# CH32V467WEU-R0.net
KiCad netlist of a schematic drawn in Altium Designer
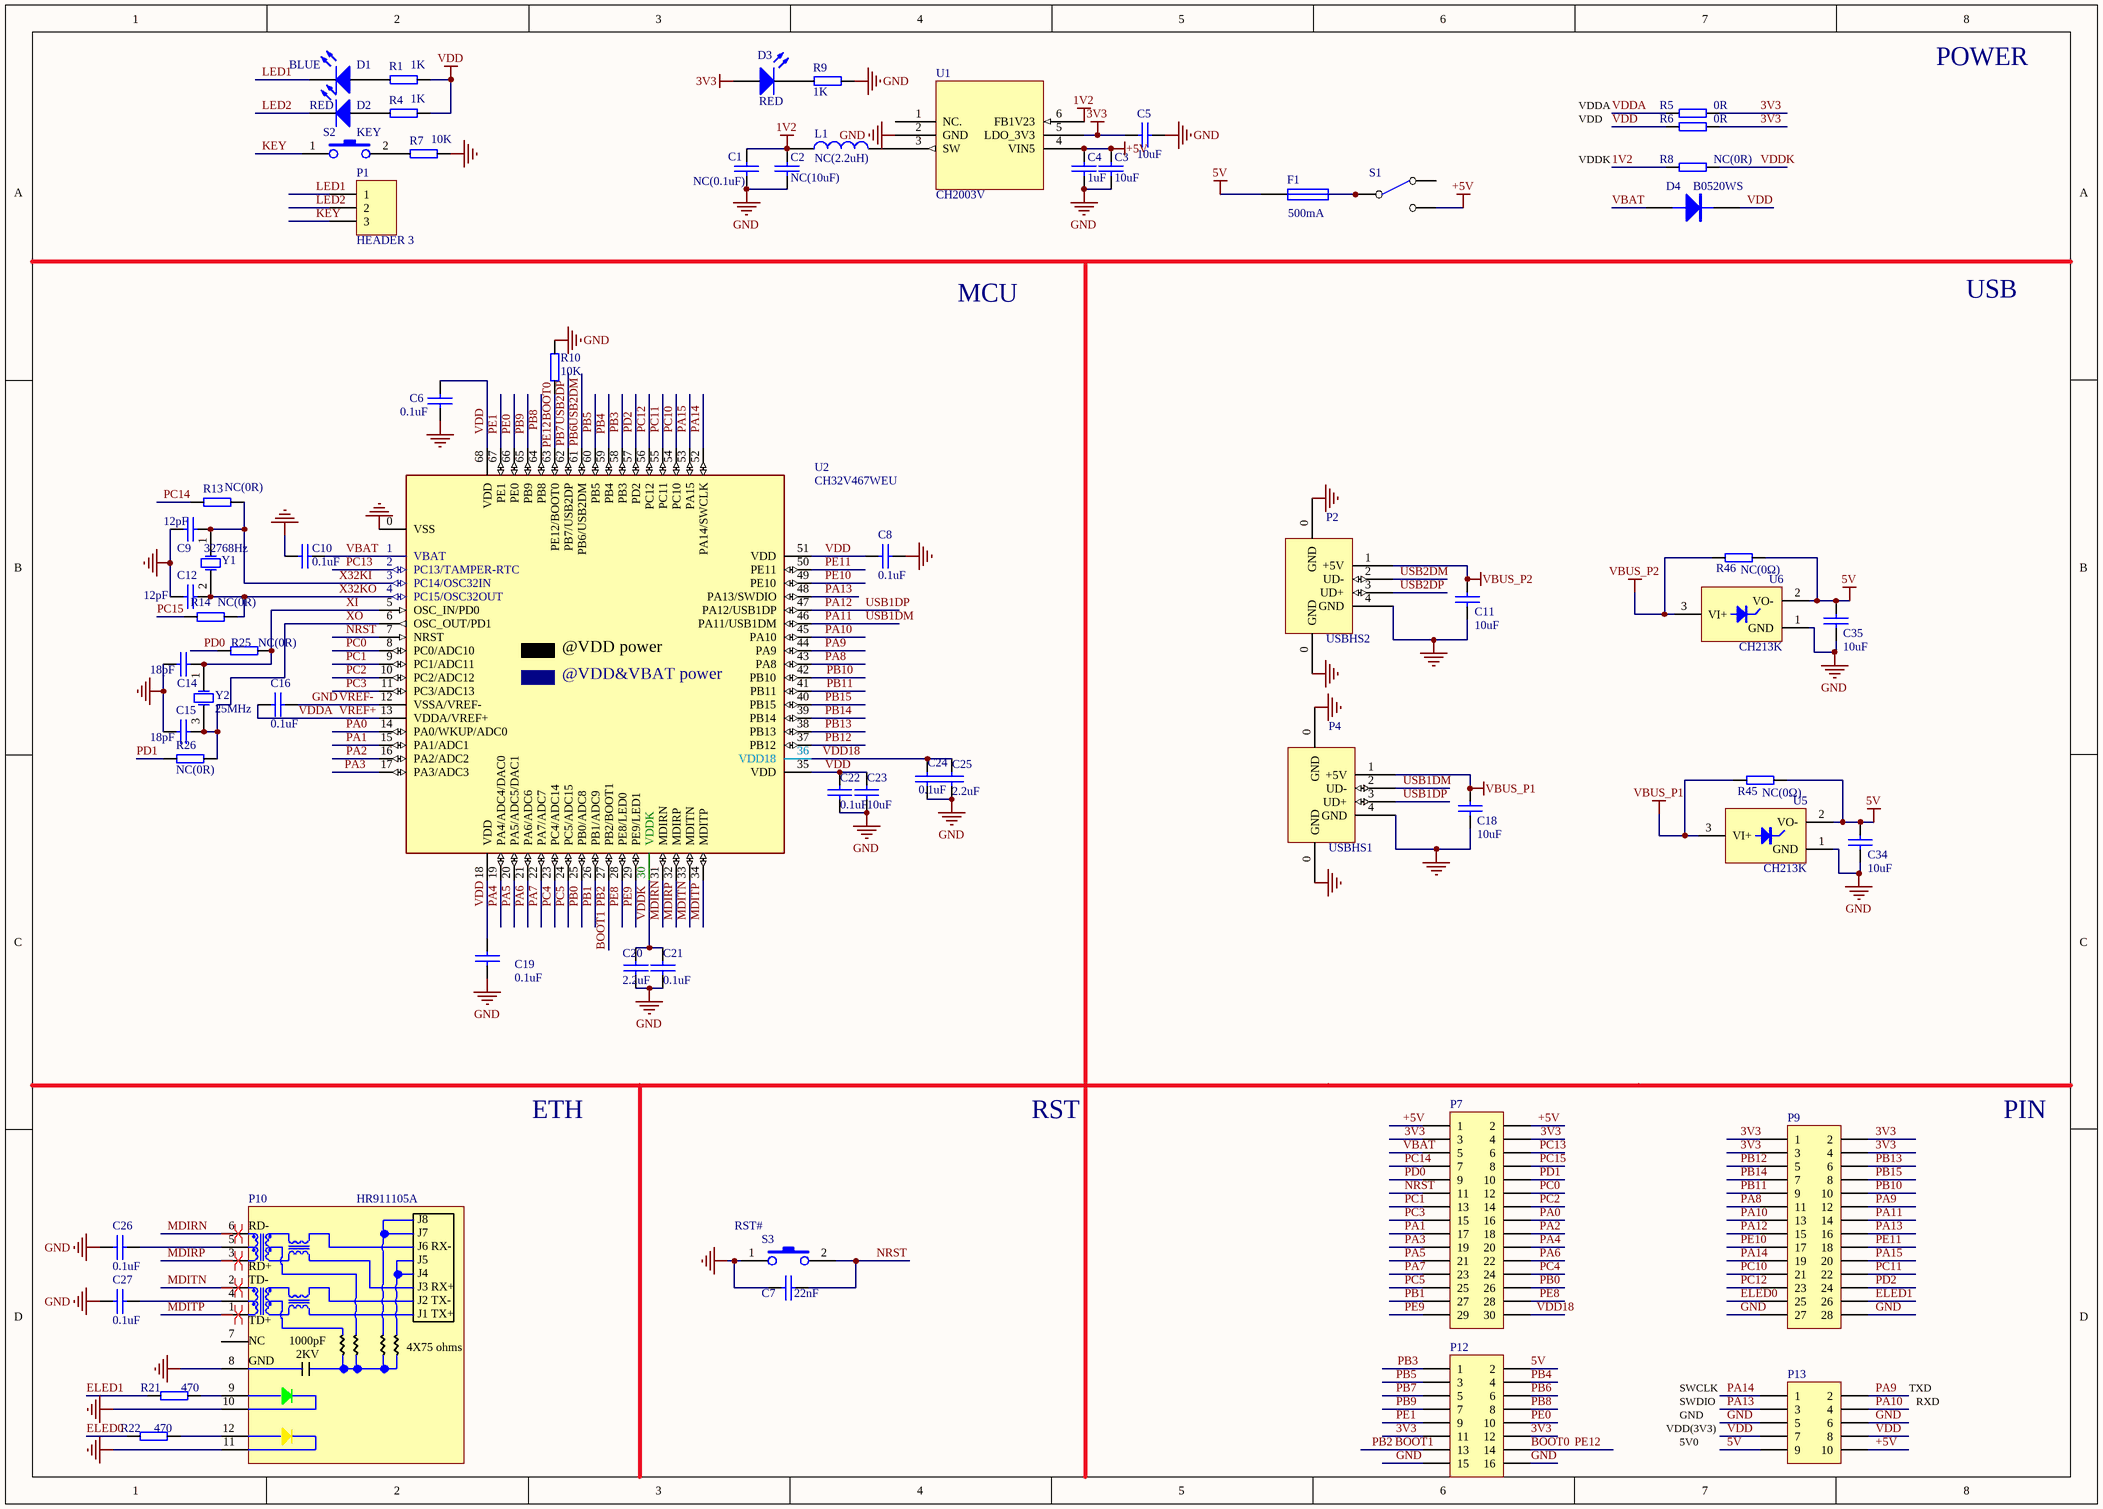
[diagram p0: CH32V467WEU-R0.SchDoc]

(export (version "E")
  (design (tool "Eeschema 10.0.6"))
  (components
    (comp (ref "C1")
      (value "NC(0.1uF)")
      (footprint "0402_C")
      (description "Capacitor")
      (libsource (lib "") (part "CAP_2"))
    )
    (comp (ref "C2")
      (value "NC(10uF)")
      (footprint "0603_C")
      (description "Capacitor")
      (libsource (lib "*") (part "CAP"))
    )
    (comp (ref "C3")
      (value "10uF")
      (footprint "0603_C")
      (description "Capacitor")
      (libsource (lib "*") (part "CAP"))
    )
    (comp (ref "C4")
      (value "1uF")
      (footprint "0402_C")
      (description "Capacitor")
      (libsource (lib "") (part "CAP_2"))
    )
    (comp (ref "C5")
      (value "10uF")
      (footprint "0603_C")
      (description "Capacitor")
      (libsource (lib "*") (part "CAP"))
    )
    (comp (ref "C6")
      (value "0.1uF")
      (footprint "0402_C")
      (description "Capacitor")
      (libsource (lib "*") (part "CAP"))
    )
    (comp (ref "C7")
      (value "22nF")
      (footprint "0402_C")
      (description "Capacitor")
      (libsource (lib "") (part "CAP_1"))
    )
    (comp (ref "C8")
      (value "0.1uF")
      (footprint "0402_C")
      (description "Capacitor")
      (libsource (lib "*") (part "CAP"))
    )
    (comp (ref "C9")
      (value "12pF")
      (footprint "0402_C")
      (description "Capacitor")
      (libsource (lib "*") (part "CAP"))
    )
    (comp (ref "C10")
      (value "0.1uF")
      (footprint "0402_C")
      (description "Capacitor")
      (libsource (lib "*") (part "CAP"))
    )
    (comp (ref "C11")
      (value "10uF")
      (footprint "0603_C")
      (description "Capacitor")
      (libsource (lib "") (part "CAP_1"))
    )
    (comp (ref "C12")
      (value "12pF")
      (footprint "0402_C")
      (description "Capacitor")
      (libsource (lib "*") (part "CAP"))
    )
    (comp (ref "C14")
      (value "18pF")
      (footprint "0402_C")
      (description "Capacitor")
      (libsource (lib "*") (part "CAP"))
    )
    (comp (ref "C15")
      (value "18pF")
      (footprint "0402_C")
      (description "Capacitor")
      (libsource (lib "*") (part "CAP"))
    )
    (comp (ref "C16")
      (value "0.1uF")
      (footprint "0402_C")
      (description "Capacitor")
      (libsource (lib "*") (part "CAP"))
    )
    (comp (ref "C18")
      (value "10uF")
      (footprint "0603_C")
      (description "Capacitor")
      (libsource (lib "") (part "CAP_1"))
    )
    (comp (ref "C19")
      (value "0.1uF")
      (footprint "0402_C")
      (description "Capacitor")
      (libsource (lib "*") (part "CAP"))
    )
    (comp (ref "C20")
      (value "2.2uF")
      (footprint "0402_C")
      (description "Capacitor")
      (libsource (lib "*") (part "CAP"))
    )
    (comp (ref "C21")
      (value "0.1uF")
      (footprint "0402_C")
      (description "Capacitor")
      (libsource (lib "*") (part "CAP"))
    )
    (comp (ref "C22")
      (value "0.1uF")
      (footprint "0402_C")
      (description "Capacitor")
      (libsource (lib "*") (part "CAP"))
    )
    (comp (ref "C23")
      (value "10uF")
      (footprint "0603_C")
      (description "Capacitor")
      (libsource (lib "*") (part "CAP"))
    )
    (comp (ref "C24")
      (value "0.1uF")
      (footprint "0402_C")
      (description "Capacitor")
      (libsource (lib "*") (part "CAP"))
    )
    (comp (ref "C25")
      (value "2.2uF")
      (footprint "0402_C")
      (description "Capacitor")
      (libsource (lib "*") (part "CAP"))
    )
    (comp (ref "C26")
      (value "0.1uF")
      (footprint "0402_C")
      (description "Capacitor")
      (libsource (lib "wch_sch_others") (part "CAP"))
    )
    (comp (ref "C27")
      (value "0.1uF")
      (footprint "0402_C")
      (description "Capacitor")
      (libsource (lib "wch_sch_others") (part "CAP"))
    )
    (comp (ref "C34")
      (value "10uF")
      (footprint "0603_C")
      (description "Capacitor")
      (libsource (lib "") (part "CAP_1"))
    )
    (comp (ref "C35")
      (value "10uF")
      (footprint "0603_C")
      (description "Capacitor")
      (libsource (lib "") (part "CAP_1"))
    )
    (comp (ref "D1")
      (value "BLUE")
      (footprint "0603+")
      (description "Typical INFRARED GaAs LED")
      (fields (field (name "PUBLISHER") "Altium Limited"))
      (libsource (lib "*") (part "LED0"))
    )
    (comp (ref "D2")
      (value "RED")
      (footprint "0603+")
      (description "Typical INFRARED GaAs LED")
      (fields (field (name "PUBLISHER") "Altium Limited"))
      (libsource (lib "*") (part "LED0"))
    )
    (comp (ref "D3")
      (value "RED")
      (footprint "0603+")
      (description "Typical INFRARED GaAs LED")
      (fields (field (name "PUBLISHER") "Altium Limited"))
      (libsource (lib "*") (part "LED0"))
    )
    (comp (ref "D4")
      (value "B0520WS")
      (footprint "SOD-323")
      (description "Diode")
      (libsource (lib "*") (part "DIODE"))
    )
    (comp (ref "F1")
      (value "500mA")
      (footprint "0603")
      (description "Fuse")
      (libsource (lib "wch_sch_others") (part "FUSE1"))
    )
    (comp (ref "L1") (value "NC(2.2uH)") (footprint "CD32") (libsource (lib "*") (part "INDUCTOR")))
    (comp (ref "P1")
      (value "HEADER 3")
      (footprint "SIP3-2.54MM")
      (description "Header, 3-Pin")
      (libsource (lib "wch_sch_others") (part "HEADER 3"))
    )
    (comp (ref "P2")
      (value "USBHS2")
      (footprint "USBAF")
      (description "USB Port")
      (libsource (lib "*") (part "USB"))
    )
    (comp (ref "P4")
      (value "USBHS1")
      (footprint "USBAF")
      (description "USB Port")
      (libsource (lib "*") (part "USB"))
    )
    (comp (ref "P7")
      (value "HEADER 15x2")
      (footprint "MYPCB:IDC30-2.54MM")
      (description "Header, 15-Pin, Dual row")
      (libsource (lib "wch_sch_others") (part "HEADER 15x2"))
    )
    (comp (ref "P9")
      (value "HEADER 14x2")
      (footprint "MYPCB:IDC28-2.54MM")
      (description "Header, 14-Pin, Dual row")
      (libsource (lib "wch_sch_others") (part "HEADER 14x2"))
    )
    (comp (ref "P10") (value "HR911105A") (footprint "HR911105A") (libsource (lib "*") (part "HR911105A")))
    (comp (ref "P12")
      (value "Ppin")
      (footprint "IDC16-2.54mm")
      (description "Header, 8-Pin, Dual row, Right Angle")
      (fields (field (name "PUBLISHER") "Altium Limited"))
      (libsource (lib "Miscellaneous Connectors") (part "Header 8X2H"))
    )
    (comp (ref "P13")
      (value "LINK")
      (footprint "IDC10-2.54mm")
      (description "Header, 5-Pin, Dual row, Right Angle")
      (fields (field (name "PUBLISHER") "Altium Limited"))
      (libsource (lib "Miscellaneous Connectors") (part "Header 5X2H"))
    )
    (comp (ref "R1") (value "1K") (footprint "0402") (libsource (lib "wch_sch_others") (part "RES")))
    (comp (ref "R4") (value "1K") (footprint "0402") (libsource (lib "wch_sch_others") (part "RES")))
    (comp (ref "R5") (value "0R") (footprint "0402") (libsource (lib "*") (part "R")))
    (comp (ref "R6") (value "0R") (footprint "0402") (libsource (lib "*") (part "R")))
    (comp (ref "R7") (value "10K") (footprint "0402") (libsource (lib "wch_sch_others") (part "RES")))
    (comp (ref "R8") (value "NC(0R)") (footprint "0402") (libsource (lib "*") (part "R")))
    (comp (ref "R9") (value "1K") (footprint "0402") (libsource (lib "wch_sch_others") (part "RES")))
    (comp (ref "R10") (value "10K") (footprint "0402") (libsource (lib "wch_sch_others") (part "RES")))
    (comp (ref "R13") (value "NC(0R)") (footprint "0402") (libsource (lib "wch_sch_others") (part "RES")))
    (comp (ref "R14") (value "NC(0R)") (footprint "0402") (libsource (lib "wch_sch_others") (part "RES")))
    (comp (ref "R21") (value "470") (footprint "0402") (libsource (lib "wch_sch_others") (part "RES")))
    (comp (ref "R22") (value "470") (footprint "0402") (libsource (lib "wch_sch_others") (part "RES")))
    (comp (ref "R25") (value "NC(0R)") (footprint "0402") (libsource (lib "wch_sch_others") (part "RES")))
    (comp (ref "R26") (value "NC(0R)") (footprint "0402") (libsource (lib "wch_sch_others") (part "RES")))
    (comp (ref "R45") (value "NC(0Ω)") (footprint "0402") (libsource (lib "wch_sch_others") (part "RES")))
    (comp (ref "R46") (value "NC(0Ω)") (footprint "0402") (libsource (lib "wch_sch_others") (part "RES")))
    (comp (ref "S1") (value "SW SPDT") (footprint "SW1") (libsource (lib "*") (part "SW SPDT")))
    (comp (ref "S2")
      (value "KEY")
      (footprint "SMD_6.1x3.65x2.5mm-KEY")
      (libsource (lib "wch_sch_others") (part "KEY1"))
    )
    (comp (ref "S3")
      (value "RST#")
      (footprint "SMD_6.1x3.65x2.5mm-KEY")
      (libsource (lib "wch_sch_others") (part "KEY1"))
    )
    (comp (ref "U1")
      (value "CH2003V")
      (footprint "SOT-23-6")
      (description "Step-Down DC-DC Converter, 5V input, 1.23V * 800mA output, with LDO 3.3V * 200mA")
      (libsource (lib "CHXXX") (part "CH2003V"))
    )
    (comp (ref "U2")
      (value "CH32V467WEU")
      (footprint "QFN68_8X8")
      (description "RISC-V FPU HD-MCU, 175MHz, USB_480M, 100M Ethernet & Phy, CAN, ADC, DAC, SRAM")
      (libsource (lib "CHXXX") (part "CH32V467WEU"))
    )
    (comp (ref "U5")
      (value "CH213K")
      (footprint "SOT-23-3")
      (description "Ideal Diode 5V*1A")
      (libsource (lib "*") (part "CH213K"))
    )
    (comp (ref "U6")
      (value "CH213K")
      (footprint "SOT-23-3")
      (description "Ideal Diode 5V*1A")
      (libsource (lib "*") (part "CH213K"))
    )
    (comp (ref "Y1")
      (value "32768Hz")
      (footprint "FC-135")
      (description "Crystal Oscillator")
      (fields (field (name "PUBLISHER") "Altium Limited"))
      (libsource (lib "") (part "XTAL_1"))
    )
    (comp (ref "Y2")
      (value "25MHz")
      (footprint "XT3225")
      (description "Crystal Oscillator")
      (fields (field (name "PUBLISHER") "Altium Limited"))
      (libsource (lib "*") (part "XTAL"))
    )
  )
  (nets
    (net (code "1") (name "+5V") (class "Default")
      (node (ref "C3") (pin "2") (pinfunction "2_2") (pintype "passive"))
      (node (ref "C4") (pin "2") (pinfunction "2_2") (pintype "passive"))
      (node (ref "P13") (pin "10") (pinfunction "10_10") (pintype "passive"))
      (node (ref "P7") (pin "1") (pinfunction "1_1") (pintype "passive"))
      (node (ref "P7") (pin "2") (pinfunction "2_2") (pintype "passive"))
      (node (ref "S1") (pin "2") (pinfunction "NC_2") (pintype "passive"))
      (node (ref "U1") (pin "4") (pinfunction "VIN5_4") (pintype "power_in"))
    )
    (net (code "3") (name "/BOOT0") (class "Default")
      (node (ref "P12") (pin "14") (pinfunction "14_14") (pintype "passive"))
      (node (ref "R10") (pin "2") (pintype "passive"))
      (node (ref "U2") (pin "63") (pinfunction "PE12/BOOT0_63") (pintype "bidirectional"))
    )
    (net (code "4") (name "/BOOT1") (class "Default")
      (node (ref "P12") (pin "13") (pinfunction "13_13") (pintype "passive"))
      (node (ref "U2") (pin "27") (pinfunction "PB2/BOOT1_27") (pintype "bidirectional"))
    )
    (net (code "5") (name "/ELED0") (class "Default")
      (node (ref "P9") (pin "25") (pinfunction "25_25") (pintype "passive"))
      (node (ref "R22") (pin "1") (pintype "passive"))
    )
    (net (code "6") (name "/ELED1") (class "Default")
      (node (ref "P9") (pin "26") (pinfunction "26_26") (pintype "passive"))
      (node (ref "R21") (pin "1") (pintype "passive"))
    )
    (net (code "7") (name "/KEY") (class "Default")
      (node (ref "P1") (pin "3") (pinfunction "3_3") (pintype "passive"))
      (node (ref "S2") (pin "1") (pinfunction "1_1") (pintype "passive"))
    )
    (net (code "8") (name "/LED1") (class "Default")
      (node (ref "D1") (pin "2") (pinfunction "K_2") (pintype "passive"))
      (node (ref "P1") (pin "1") (pinfunction "1_1") (pintype "passive"))
    )
    (net (code "9") (name "/LED2") (class "Default")
      (node (ref "D2") (pin "2") (pinfunction "K_2") (pintype "passive"))
      (node (ref "P1") (pin "2") (pinfunction "2_2") (pintype "passive"))
    )
    (net (code "10") (name "/MDIRN") (class "Default")
      (node (ref "P10") (pin "6") (pintype "passive"))
      (node (ref "U2") (pin "31") (pinfunction "MDIRN_31") (pintype "bidirectional"))
    )
    (net (code "11") (name "/MDIRP") (class "Default")
      (node (ref "P10") (pin "3") (pintype "passive"))
      (node (ref "U2") (pin "32") (pinfunction "MDIRP_32") (pintype "bidirectional"))
    )
    (net (code "12") (name "/MDITN") (class "Default")
      (node (ref "P10") (pin "2") (pintype "passive"))
      (node (ref "U2") (pin "33") (pinfunction "MDITN_33") (pintype "bidirectional"))
    )
    (net (code "13") (name "/MDITP") (class "Default")
      (node (ref "P10") (pin "1") (pintype "passive"))
      (node (ref "U2") (pin "34") (pinfunction "MDITP_34") (pintype "bidirectional"))
    )
    (net (code "14") (name "/NRST") (class "Default")
      (node (ref "C7") (pin "2") (pinfunction "2_2") (pintype "passive"))
      (node (ref "P7") (pin "11") (pinfunction "11_11") (pintype "passive"))
      (node (ref "S3") (pin "2") (pinfunction "2_2") (pintype "passive"))
      (node (ref "U2") (pin "7") (pinfunction "NRST_7") (pintype "input"))
    )
    (net (code "15") (name "/PA0") (class "Default")
      (node (ref "P7") (pin "16") (pinfunction "16_16") (pintype "passive"))
      (node (ref "U2") (pin "14") (pinfunction "PA0/WKUP/ADC0_14") (pintype "bidirectional"))
    )
    (net (code "16") (name "/PA1") (class "Default")
      (node (ref "P7") (pin "17") (pinfunction "17_17") (pintype "passive"))
      (node (ref "U2") (pin "15") (pinfunction "PA1/ADC1_15") (pintype "bidirectional"))
    )
    (net (code "17") (name "/PA2") (class "Default")
      (node (ref "P7") (pin "18") (pinfunction "18_18") (pintype "passive"))
      (node (ref "U2") (pin "16") (pinfunction "PA2/ADC2_16") (pintype "bidirectional"))
    )
    (net (code "18") (name "/PA3") (class "Default")
      (node (ref "P7") (pin "19") (pinfunction "19_19") (pintype "passive"))
      (node (ref "U2") (pin "17") (pinfunction "PA3/ADC3_17") (pintype "bidirectional"))
    )
    (net (code "19") (name "/PA4") (class "Default")
      (node (ref "P7") (pin "20") (pinfunction "20_20") (pintype "passive"))
      (node (ref "U2") (pin "19") (pinfunction "PA4/ADC4/DAC0_19") (pintype "bidirectional"))
    )
    (net (code "20") (name "/PA5") (class "Default")
      (node (ref "P7") (pin "21") (pinfunction "21_21") (pintype "passive"))
      (node (ref "U2") (pin "20") (pinfunction "PA5/ADC5/DAC1_20") (pintype "bidirectional"))
    )
    (net (code "21") (name "/PA6") (class "Default")
      (node (ref "P7") (pin "22") (pinfunction "22_22") (pintype "passive"))
      (node (ref "U2") (pin "21") (pinfunction "PA6/ADC6_21") (pintype "bidirectional"))
    )
    (net (code "22") (name "/PA7") (class "Default")
      (node (ref "P7") (pin "23") (pinfunction "23_23") (pintype "passive"))
      (node (ref "U2") (pin "22") (pinfunction "PA7/ADC7_22") (pintype "bidirectional"))
    )
    (net (code "23") (name "/PA8") (class "Default")
      (node (ref "P9") (pin "11") (pinfunction "11_11") (pintype "passive"))
      (node (ref "U2") (pin "43") (pinfunction "PA8_43") (pintype "bidirectional"))
    )
    (net (code "24") (name "/PA9") (class "Default")
      (node (ref "P13") (pin "2") (pinfunction "2_2") (pintype "passive"))
      (node (ref "P9") (pin "12") (pinfunction "12_12") (pintype "passive"))
      (node (ref "U2") (pin "44") (pinfunction "PA9_44") (pintype "bidirectional"))
    )
    (net (code "25") (name "/PA10") (class "Default")
      (node (ref "P13") (pin "4") (pinfunction "4_4") (pintype "passive"))
      (node (ref "P9") (pin "13") (pinfunction "13_13") (pintype "passive"))
      (node (ref "U2") (pin "45") (pinfunction "PA10_45") (pintype "bidirectional"))
    )
    (net (code "26") (name "/PA11") (class "Default")
      (node (ref "P4") (pin "2") (pinfunction "UD-_2") (pintype "bidirectional"))
      (node (ref "P9") (pin "14") (pinfunction "14_14") (pintype "passive"))
      (node (ref "U2") (pin "46") (pinfunction "PA11/USB1DM_46") (pintype "bidirectional"))
    )
    (net (code "27") (name "/PA12") (class "Default")
      (node (ref "P4") (pin "3") (pinfunction "UD+_3") (pintype "bidirectional"))
      (node (ref "P9") (pin "15") (pinfunction "15_15") (pintype "passive"))
      (node (ref "U2") (pin "47") (pinfunction "PA12/USB1DP_47") (pintype "bidirectional"))
    )
    (net (code "28") (name "/PA13") (class "Default")
      (node (ref "P13") (pin "3") (pinfunction "3_3") (pintype "passive"))
      (node (ref "P9") (pin "16") (pinfunction "16_16") (pintype "passive"))
      (node (ref "U2") (pin "48") (pinfunction "PA13/SWDIO_48") (pintype "bidirectional"))
    )
    (net (code "29") (name "/PA14") (class "Default")
      (node (ref "P13") (pin "1") (pinfunction "1_1") (pintype "passive"))
      (node (ref "P9") (pin "19") (pinfunction "19_19") (pintype "passive"))
      (node (ref "U2") (pin "52") (pinfunction "PA14/SWCLK_52") (pintype "bidirectional"))
    )
    (net (code "30") (name "/PA15") (class "Default")
      (node (ref "P9") (pin "20") (pinfunction "20_20") (pintype "passive"))
      (node (ref "U2") (pin "53") (pinfunction "PA15_53") (pintype "bidirectional"))
    )
    (net (code "31") (name "/PB0") (class "Default")
      (node (ref "P7") (pin "26") (pinfunction "26_26") (pintype "passive"))
      (node (ref "U2") (pin "25") (pinfunction "PB0/ADC8_25") (pintype "bidirectional"))
    )
    (net (code "32") (name "/PB1") (class "Default")
      (node (ref "P7") (pin "27") (pinfunction "27_27") (pintype "passive"))
      (node (ref "U2") (pin "26") (pinfunction "PB1/ADC9_26") (pintype "bidirectional"))
    )
    (net (code "33") (name "/PB3") (class "Default")
      (node (ref "P12") (pin "1") (pinfunction "1_1") (pintype "passive"))
      (node (ref "U2") (pin "58") (pinfunction "PB3_58") (pintype "bidirectional"))
    )
    (net (code "34") (name "/PB4") (class "Default")
      (node (ref "P12") (pin "4") (pinfunction "4_4") (pintype "passive"))
      (node (ref "U2") (pin "59") (pinfunction "PB4_59") (pintype "bidirectional"))
    )
    (net (code "35") (name "/PB5") (class "Default")
      (node (ref "P12") (pin "3") (pinfunction "3_3") (pintype "passive"))
      (node (ref "U2") (pin "60") (pinfunction "PB5_60") (pintype "bidirectional"))
    )
    (net (code "36") (name "/PB6") (class "Default")
      (node (ref "P12") (pin "6") (pinfunction "6_6") (pintype "passive"))
      (node (ref "P2") (pin "2") (pinfunction "UD-_2") (pintype "bidirectional"))
      (node (ref "U2") (pin "61") (pinfunction "PB6/USB2DM_61") (pintype "bidirectional"))
    )
    (net (code "37") (name "/PB7") (class "Default")
      (node (ref "P12") (pin "5") (pinfunction "5_5") (pintype "passive"))
      (node (ref "P2") (pin "3") (pinfunction "UD+_3") (pintype "bidirectional"))
      (node (ref "U2") (pin "62") (pinfunction "PB7/USB2DP_62") (pintype "bidirectional"))
    )
    (net (code "38") (name "/PB8") (class "Default")
      (node (ref "P12") (pin "8") (pinfunction "8_8") (pintype "passive"))
      (node (ref "U2") (pin "64") (pinfunction "PB8_64") (pintype "bidirectional"))
    )
    (net (code "39") (name "/PB9") (class "Default")
      (node (ref "P12") (pin "7") (pinfunction "7_7") (pintype "passive"))
      (node (ref "U2") (pin "65") (pinfunction "PB9_65") (pintype "bidirectional"))
    )
    (net (code "40") (name "/PB10") (class "Default")
      (node (ref "P9") (pin "10") (pinfunction "10_10") (pintype "passive"))
      (node (ref "U2") (pin "42") (pinfunction "PB10_42") (pintype "bidirectional"))
    )
    (net (code "41") (name "/PB11") (class "Default")
      (node (ref "P9") (pin "9") (pinfunction "9_9") (pintype "passive"))
      (node (ref "U2") (pin "41") (pinfunction "PB11_41") (pintype "bidirectional"))
    )
    (net (code "42") (name "/PB12") (class "Default")
      (node (ref "P9") (pin "5") (pinfunction "5_5") (pintype "passive"))
      (node (ref "U2") (pin "37") (pinfunction "PB12_37") (pintype "bidirectional"))
    )
    (net (code "43") (name "/PB13") (class "Default")
      (node (ref "P9") (pin "6") (pinfunction "6_6") (pintype "passive"))
      (node (ref "U2") (pin "38") (pinfunction "PB13_38") (pintype "bidirectional"))
    )
    (net (code "44") (name "/PB14") (class "Default")
      (node (ref "P9") (pin "7") (pinfunction "7_7") (pintype "passive"))
      (node (ref "U2") (pin "39") (pinfunction "PB14_39") (pintype "bidirectional"))
    )
    (net (code "45") (name "/PB15") (class "Default")
      (node (ref "P9") (pin "8") (pinfunction "8_8") (pintype "passive"))
      (node (ref "U2") (pin "40") (pinfunction "PB15_40") (pintype "bidirectional"))
    )
    (net (code "46") (name "/PC0") (class "Default")
      (node (ref "P7") (pin "12") (pinfunction "12_12") (pintype "passive"))
      (node (ref "U2") (pin "8") (pinfunction "PC0/ADC10_8") (pintype "bidirectional"))
    )
    (net (code "47") (name "/PC1") (class "Default")
      (node (ref "P7") (pin "13") (pinfunction "13_13") (pintype "passive"))
      (node (ref "U2") (pin "9") (pinfunction "PC1/ADC11_9") (pintype "bidirectional"))
    )
    (net (code "48") (name "/PC2") (class "Default")
      (node (ref "P7") (pin "14") (pinfunction "14_14") (pintype "passive"))
      (node (ref "U2") (pin "10") (pinfunction "PC2/ADC12_10") (pintype "bidirectional"))
    )
    (net (code "49") (name "/PC3") (class "Default")
      (node (ref "P7") (pin "15") (pinfunction "15_15") (pintype "passive"))
      (node (ref "U2") (pin "11") (pinfunction "PC3/ADC13_11") (pintype "bidirectional"))
    )
    (net (code "50") (name "/PC4") (class "Default")
      (node (ref "P7") (pin "24") (pinfunction "24_24") (pintype "passive"))
      (node (ref "U2") (pin "23") (pinfunction "PC4/ADC14_23") (pintype "bidirectional"))
    )
    (net (code "51") (name "/PC5") (class "Default")
      (node (ref "P7") (pin "25") (pinfunction "25_25") (pintype "passive"))
      (node (ref "U2") (pin "24") (pinfunction "PC5/ADC15_24") (pintype "bidirectional"))
    )
    (net (code "52") (name "/PC10") (class "Default")
      (node (ref "P9") (pin "21") (pinfunction "21_21") (pintype "passive"))
      (node (ref "U2") (pin "54") (pinfunction "PC10_54") (pintype "bidirectional"))
    )
    (net (code "53") (name "/PC11") (class "Default")
      (node (ref "P9") (pin "22") (pinfunction "22_22") (pintype "passive"))
      (node (ref "U2") (pin "55") (pinfunction "PC11_55") (pintype "bidirectional"))
    )
    (net (code "54") (name "/PC12") (class "Default")
      (node (ref "P9") (pin "23") (pinfunction "23_23") (pintype "passive"))
      (node (ref "U2") (pin "56") (pinfunction "PC12_56") (pintype "bidirectional"))
    )
    (net (code "55") (name "/PC13") (class "Default")
      (node (ref "P7") (pin "6") (pinfunction "6_6") (pintype "passive"))
      (node (ref "U2") (pin "2") (pinfunction "PC13/TAMPER-RTC_2") (pintype "bidirectional"))
    )
    (net (code "56") (name "/PC14") (class "Default")
      (node (ref "P7") (pin "7") (pinfunction "7_7") (pintype "passive"))
      (node (ref "R13") (pin "1") (pintype "passive"))
    )
    (net (code "57") (name "/PC15") (class "Default")
      (node (ref "P7") (pin "8") (pinfunction "8_8") (pintype "passive"))
      (node (ref "R14") (pin "1") (pintype "passive"))
    )
    (net (code "58") (name "/PD0") (class "Default")
      (node (ref "P7") (pin "9") (pinfunction "9_9") (pintype "passive"))
      (node (ref "R25") (pin "1") (pintype "passive"))
    )
    (net (code "59") (name "/PD1") (class "Default")
      (node (ref "P7") (pin "10") (pinfunction "10_10") (pintype "passive"))
      (node (ref "R26") (pin "2") (pintype "passive"))
    )
    (net (code "60") (name "/PD2") (class "Default")
      (node (ref "P9") (pin "24") (pinfunction "24_24") (pintype "passive"))
      (node (ref "U2") (pin "57") (pinfunction "PD2_57") (pintype "bidirectional"))
    )
    (net (code "61") (name "/PE0") (class "Default")
      (node (ref "P12") (pin "10") (pinfunction "10_10") (pintype "passive"))
      (node (ref "U2") (pin "66") (pinfunction "PE0_66") (pintype "bidirectional"))
    )
    (net (code "62") (name "/PE1") (class "Default")
      (node (ref "P12") (pin "9") (pinfunction "9_9") (pintype "passive"))
      (node (ref "U2") (pin "67") (pinfunction "PE1_67") (pintype "bidirectional"))
    )
    (net (code "63") (name "/PE8") (class "Default")
      (node (ref "P7") (pin "28") (pinfunction "28_28") (pintype "passive"))
      (node (ref "U2") (pin "28") (pinfunction "PE8/LED0_28") (pintype "bidirectional"))
    )
    (net (code "64") (name "/PE9") (class "Default")
      (node (ref "P7") (pin "29") (pinfunction "29_29") (pintype "passive"))
      (node (ref "U2") (pin "29") (pinfunction "PE9/LED1_29") (pintype "bidirectional"))
    )
    (net (code "65") (name "/PE10") (class "Default")
      (node (ref "P9") (pin "17") (pinfunction "17_17") (pintype "passive"))
      (node (ref "U2") (pin "49") (pinfunction "PE10_49") (pintype "bidirectional"))
    )
    (net (code "66") (name "/PE11") (class "Default")
      (node (ref "P9") (pin "18") (pinfunction "18_18") (pintype "passive"))
      (node (ref "U2") (pin "50") (pinfunction "PE11_50") (pintype "bidirectional"))
    )
    (net (code "67") (name "/VBAT") (class "Default")
      (node (ref "C10") (pin "2") (pinfunction "2_2") (pintype "passive"))
      (node (ref "D4") (pin "1") (pinfunction "A_1") (pintype "passive"))
      (node (ref "P7") (pin "5") (pinfunction "5_5") (pintype "passive"))
      (node (ref "U2") (pin "1") (pinfunction "VBAT_1") (pintype "power_in"))
    )
    (net (code "68") (name "/VDD18") (class "Default")
      (node (ref "C24") (pin "2") (pinfunction "2_2") (pintype "passive"))
      (node (ref "C25") (pin "2") (pinfunction "2_2") (pintype "passive"))
      (node (ref "P7") (pin "30") (pinfunction "30_30") (pintype "passive"))
      (node (ref "U2") (pin "36") (pinfunction "VDD18_36") (pintype "power_in"))
    )
    (net (code "69") (name "/VDDA") (class "Default")
      (node (ref "C16") (pin "1") (pinfunction "1_1") (pintype "passive"))
      (node (ref "R5") (pin "2") (pinfunction "2_2") (pintype "passive"))
      (node (ref "U2") (pin "13") (pinfunction "VDDA/VREF+_13") (pintype "power_in"))
    )
    (net (code "70") (name "/VDDK") (class "Default")
      (node (ref "C20") (pin "2") (pinfunction "2_2") (pintype "passive"))
      (node (ref "C21") (pin "2") (pinfunction "2_2") (pintype "passive"))
      (node (ref "R8") (pin "1") (pinfunction "1_1") (pintype "passive"))
      (node (ref "U2") (pin "30") (pinfunction "VDDK_30") (pintype "power_in"))
    )
    (net (code "71") (name "/X32KI") (class "Default")
      (node (ref "C9") (pin "2") (pinfunction "2_2") (pintype "passive"))
      (node (ref "R13") (pin "2") (pintype "passive"))
      (node (ref "U2") (pin "3") (pinfunction "PC14/OSC32IN_3") (pintype "bidirectional"))
      (node (ref "Y1") (pin "1") (pinfunction "OSC1_1") (pintype "passive"))
    )
    (net (code "72") (name "/X32KO") (class "Default")
      (node (ref "C12") (pin "2") (pinfunction "2_2") (pintype "passive"))
      (node (ref "R14") (pin "2") (pintype "passive"))
      (node (ref "U2") (pin "4") (pinfunction "PC15/OSC32OUT_4") (pintype "bidirectional"))
      (node (ref "Y1") (pin "2") (pinfunction "OSC2_2") (pintype "passive"))
    )
    (net (code "73") (name "/XI") (class "Default")
      (node (ref "C14") (pin "2") (pinfunction "2_2") (pintype "passive"))
      (node (ref "R25") (pin "2") (pintype "passive"))
      (node (ref "U2") (pin "5") (pinfunction "OSC_IN/PD0_5") (pintype "input"))
      (node (ref "Y2") (pin "1") (pinfunction "OSC1_1") (pintype "passive"))
    )
    (net (code "74") (name "/XO") (class "Default")
      (node (ref "C15") (pin "2") (pinfunction "2_2") (pintype "passive"))
      (node (ref "R26") (pin "1") (pintype "passive"))
      (node (ref "U2") (pin "6") (pinfunction "OSC_OUT/PD1_6") (pintype "output"))
      (node (ref "Y2") (pin "3") (pinfunction "OSC2_3") (pintype "passive"))
    )
    (net (code "75") (name "1V2") (class "Default")
      (node (ref "C1") (pin "2") (pinfunction "2_2") (pintype "passive"))
      (node (ref "C2") (pin "2") (pinfunction "2_2") (pintype "passive"))
      (node (ref "L1") (pin "2") (pinfunction "2_2") (pintype "passive"))
      (node (ref "R8") (pin "2") (pinfunction "2_2") (pintype "passive"))
      (node (ref "U1") (pin "6") (pinfunction "FB1V23_6") (pintype "input"))
    )
    (net (code "76") (name "3V3") (class "Default")
      (node (ref "C5") (pin "2") (pinfunction "2_2") (pintype "passive"))
      (node (ref "D3") (pin "1") (pinfunction "A_1") (pintype "passive"))
      (node (ref "P12") (pin "11") (pinfunction "11_11") (pintype "passive"))
      (node (ref "P12") (pin "12") (pinfunction "12_12") (pintype "passive"))
      (node (ref "P7") (pin "3") (pinfunction "3_3") (pintype "passive"))
      (node (ref "P7") (pin "4") (pinfunction "4_4") (pintype "passive"))
      (node (ref "P9") (pin "1") (pinfunction "1_1") (pintype "passive"))
      (node (ref "P9") (pin "2") (pinfunction "2_2") (pintype "passive"))
      (node (ref "P9") (pin "3") (pinfunction "3_3") (pintype "passive"))
      (node (ref "P9") (pin "4") (pinfunction "4_4") (pintype "passive"))
      (node (ref "R5") (pin "1") (pinfunction "1_1") (pintype "passive"))
      (node (ref "R6") (pin "1") (pinfunction "1_1") (pintype "passive"))
      (node (ref "U1") (pin "5") (pinfunction "LDO_3V3_5") (pintype "power_in"))
    )
    (net (code "77") (name "5V") (class "Default")
      (node (ref "C34") (pin "1") (pinfunction "1_1") (pintype "passive"))
      (node (ref "C35") (pin "1") (pinfunction "1_1") (pintype "passive"))
      (node (ref "F1") (pin "1") (pinfunction "1_1") (pintype "passive"))
      (node (ref "P12") (pin "2") (pinfunction "2_2") (pintype "passive"))
      (node (ref "P13") (pin "9") (pinfunction "9_9") (pintype "passive"))
      (node (ref "R45") (pin "1") (pintype "passive"))
      (node (ref "R46") (pin "1") (pintype "passive"))
      (node (ref "U5") (pin "2") (pinfunction "VO-_2") (pintype "power_in"))
      (node (ref "U6") (pin "2") (pinfunction "VO-_2") (pintype "power_in"))
    )
    (net (code "78") (name "GND") (class "Default")
      (node (ref "C1") (pin "1") (pinfunction "1_1") (pintype "passive"))
      (node (ref "C10") (pin "1") (pinfunction "1_1") (pintype "passive"))
      (node (ref "C11") (pin "2") (pinfunction "2_2") (pintype "passive"))
      (node (ref "C12") (pin "1") (pinfunction "1_1") (pintype "passive"))
      (node (ref "C14") (pin "1") (pinfunction "1_1") (pintype "passive"))
      (node (ref "C15") (pin "1") (pinfunction "1_1") (pintype "passive"))
      (node (ref "C16") (pin "2") (pinfunction "2_2") (pintype "passive"))
      (node (ref "C18") (pin "2") (pinfunction "2_2") (pintype "passive"))
      (node (ref "C19") (pin "1") (pinfunction "1_1") (pintype "passive"))
      (node (ref "C2") (pin "1") (pinfunction "1_1") (pintype "passive"))
      (node (ref "C20") (pin "1") (pinfunction "1_1") (pintype "passive"))
      (node (ref "C21") (pin "1") (pinfunction "1_1") (pintype "passive"))
      (node (ref "C22") (pin "1") (pinfunction "1_1") (pintype "passive"))
      (node (ref "C23") (pin "1") (pinfunction "1_1") (pintype "passive"))
      (node (ref "C24") (pin "1") (pinfunction "1_1") (pintype "passive"))
      (node (ref "C25") (pin "1") (pinfunction "1_1") (pintype "passive"))
      (node (ref "C26") (pin "1") (pinfunction "1_1") (pintype "passive"))
      (node (ref "C27") (pin "1") (pinfunction "1_1") (pintype "passive"))
      (node (ref "C3") (pin "1") (pinfunction "1_1") (pintype "passive"))
      (node (ref "C34") (pin "2") (pinfunction "2_2") (pintype "passive"))
      (node (ref "C35") (pin "2") (pinfunction "2_2") (pintype "passive"))
      (node (ref "C4") (pin "1") (pinfunction "1_1") (pintype "passive"))
      (node (ref "C5") (pin "1") (pinfunction "1_1") (pintype "passive"))
      (node (ref "C6") (pin "1") (pinfunction "1_1") (pintype "passive"))
      (node (ref "C7") (pin "1") (pinfunction "1_1") (pintype "passive"))
      (node (ref "C8") (pin "2") (pinfunction "2_2") (pintype "passive"))
      (node (ref "C9") (pin "1") (pinfunction "1_1") (pintype "passive"))
      (node (ref "P10") (pin "10") (pintype "passive"))
      (node (ref "P10") (pin "11") (pintype "passive"))
      (node (ref "P10") (pin "8") (pintype "passive"))
      (node (ref "P12") (pin "15") (pinfunction "15_15") (pintype "passive"))
      (node (ref "P12") (pin "16") (pinfunction "16_16") (pintype "passive"))
      (node (ref "P13") (pin "5") (pinfunction "5_5") (pintype "passive"))
      (node (ref "P13") (pin "6") (pinfunction "6_6") (pintype "passive"))
      (node (ref "P2") (pin "0") (pinfunction "GND_0") (pintype "power_in"))
      (node (ref "P2") (pin "4") (pinfunction "GND_4") (pintype "power_in"))
      (node (ref "P4") (pin "0") (pinfunction "GND_0") (pintype "power_in"))
      (node (ref "P4") (pin "4") (pinfunction "GND_4") (pintype "power_in"))
      (node (ref "P9") (pin "27") (pinfunction "27_27") (pintype "passive"))
      (node (ref "P9") (pin "28") (pinfunction "28_28") (pintype "passive"))
      (node (ref "R10") (pin "1") (pintype "passive"))
      (node (ref "R7") (pin "1") (pintype "passive"))
      (node (ref "R9") (pin "2") (pintype "passive"))
      (node (ref "S3") (pin "1") (pinfunction "1_1") (pintype "passive"))
      (node (ref "U1") (pin "2") (pinfunction "GND_2") (pintype "power_in"))
      (node (ref "U2") (pin "0") (pinfunction "VSS_0") (pintype "power_in"))
      (node (ref "U2") (pin "12") (pinfunction "VSSA/VREF-_12") (pintype "power_in"))
      (node (ref "U5") (pin "1") (pinfunction "GND_1") (pintype "power_in"))
      (node (ref "U6") (pin "1") (pinfunction "GND_1") (pintype "power_in"))
    )
    (net (code "79") (name "Net-(C26-Pad2)") (class "Default")
      (node (ref "C26") (pin "2") (pinfunction "2_2") (pintype "passive"))
      (node (ref "P10") (pin "5") (pintype "passive"))
    )
    (net (code "80") (name "Net-(C27-Pad2)") (class "Default")
      (node (ref "C27") (pin "2") (pinfunction "2_2") (pintype "passive"))
      (node (ref "P10") (pin "4") (pintype "passive"))
    )
    (net (code "81") (name "Net-(D1-A)") (class "Default")
      (node (ref "D1") (pin "1") (pinfunction "A_1") (pintype "passive"))
      (node (ref "R1") (pin "2") (pintype "passive"))
    )
    (net (code "82") (name "Net-(D2-A)") (class "Default")
      (node (ref "D2") (pin "1") (pinfunction "A_1") (pintype "passive"))
      (node (ref "R4") (pin "2") (pintype "passive"))
    )
    (net (code "83") (name "Net-(D3-K)") (class "Default")
      (node (ref "D3") (pin "2") (pinfunction "K_2") (pintype "passive"))
      (node (ref "R9") (pin "1") (pintype "passive"))
    )
    (net (code "84") (name "Net-(P10-Pad9)") (class "Default")
      (node (ref "P10") (pin "9") (pintype "passive"))
      (node (ref "R21") (pin "2") (pintype "passive"))
    )
    (net (code "85") (name "Net-(P10-Pad12)") (class "Default")
      (node (ref "P10") (pin "12") (pintype "passive"))
      (node (ref "R22") (pin "2") (pintype "passive"))
    )
    (net (code "86") (name "Net-(R7-Pad2)") (class "Default")
      (node (ref "R7") (pin "2") (pintype "passive"))
      (node (ref "S2") (pin "2") (pinfunction "2_2") (pintype "passive"))
    )
    (net (code "87") (name "Net-(S1-COMMON)") (class "Default")
      (node (ref "F1") (pin "2") (pinfunction "2_2") (pintype "passive"))
      (node (ref "S1") (pin "1") (pinfunction "COMMON_1") (pintype "passive"))
    )
    (net (code "88") (name "Net-(U1-SW)") (class "Default")
      (node (ref "L1") (pin "1") (pinfunction "1_1") (pintype "passive"))
      (node (ref "U1") (pin "3") (pinfunction "SW_3") (pintype "output"))
    )
    (net (code "89") (name "VBUS_P1") (class "Default")
      (node (ref "C18") (pin "1") (pinfunction "1_1") (pintype "passive"))
      (node (ref "P4") (pin "1") (pinfunction "+5V_1") (pintype "power_in"))
      (node (ref "R45") (pin "2") (pintype "passive"))
      (node (ref "U5") (pin "3") (pinfunction "VI+_3") (pintype "power_in"))
    )
    (net (code "90") (name "VBUS_P2") (class "Default")
      (node (ref "C11") (pin "1") (pinfunction "1_1") (pintype "passive"))
      (node (ref "P2") (pin "1") (pinfunction "+5V_1") (pintype "power_in"))
      (node (ref "R46") (pin "2") (pintype "passive"))
      (node (ref "U6") (pin "3") (pinfunction "VI+_3") (pintype "power_in"))
    )
    (net (code "91") (name "VDD") (class "Default")
      (node (ref "C19") (pin "2") (pinfunction "2_2") (pintype "passive"))
      (node (ref "C22") (pin "2") (pinfunction "2_2") (pintype "passive"))
      (node (ref "C23") (pin "2") (pinfunction "2_2") (pintype "passive"))
      (node (ref "C6") (pin "2") (pinfunction "2_2") (pintype "passive"))
      (node (ref "C8") (pin "1") (pinfunction "1_1") (pintype "passive"))
      (node (ref "D4") (pin "2") (pinfunction "K_2") (pintype "passive"))
      (node (ref "P13") (pin "7") (pinfunction "7_7") (pintype "passive"))
      (node (ref "P13") (pin "8") (pinfunction "8_8") (pintype "passive"))
      (node (ref "R1") (pin "1") (pintype "passive"))
      (node (ref "R4") (pin "1") (pintype "passive"))
      (node (ref "R6") (pin "2") (pinfunction "2_2") (pintype "passive"))
      (node (ref "U2") (pin "18") (pinfunction "VDD_18") (pintype "power_in"))
      (node (ref "U2") (pin "35") (pinfunction "VDD_35") (pintype "power_in"))
      (node (ref "U2") (pin "51") (pinfunction "VDD_51") (pintype "power_in"))
      (node (ref "U2") (pin "68") (pinfunction "VDD_68") (pintype "power_in"))
    )
    (net (code "92") (name "unconnected-(P10-Pad7)") (class "Default")
      (node (ref "P10") (pin "7") (pintype "passive"))
    )
    (net (code "93") (name "unconnected-(S1-NO-Pad3)") (class "Default")
      (node (ref "S1") (pin "3") (pinfunction "NO_3") (pintype "passive"))
    )
    (net (code "94") (name "unconnected-(U1-NC.-Pad1)") (class "Default")
      (node (ref "U1") (pin "1") (pinfunction "NC._1") (pintype "passive"))
    )
  )
)
